# MO-v2-5_MOD-Strips.net
KiCad netlist of a schematic drawn in EAGLE
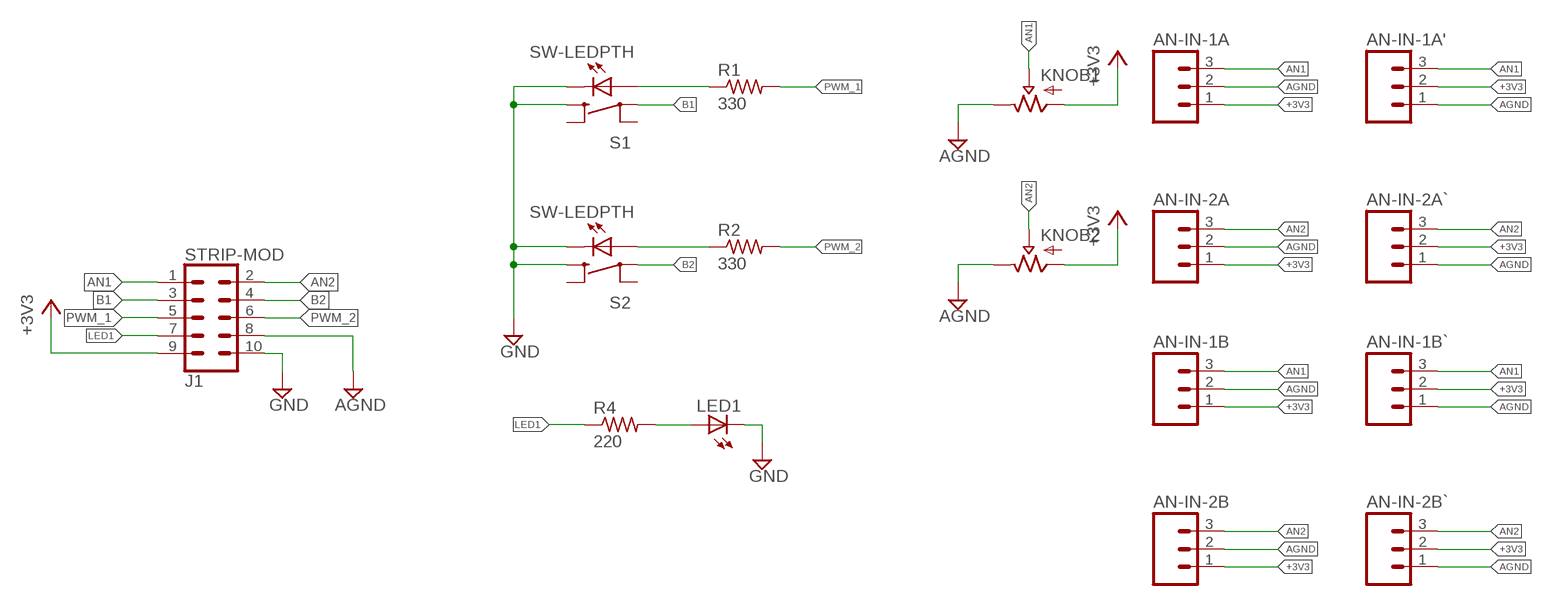
[diagram p0: schematic, sheet 1]

(export (version "E")
  (design (tool "Eeschema 10.0.6"))
  (components
    (comp (ref "AN-IN-1A")
      (value "M031X03_NO_SILK")
      (footprint "eagle-import:1X03_NO_SILK")
      (libsource (lib "eagle-import") (part "M031X03_NO_SILK"))
    )
    (comp (ref "AN-IN-1A'")
      (value "M031X03_NO_SILK")
      (footprint "eagle-import:1X03_NO_SILK")
      (libsource (lib "eagle-import") (part "M031X03_NO_SILK"))
    )
    (comp (ref "AN-IN-1B")
      (value "M031X03_NO_SILK")
      (footprint "eagle-import:1X03_NO_SILK")
      (libsource (lib "eagle-import") (part "M031X03_NO_SILK"))
    )
    (comp (ref "AN-IN-1B`")
      (value "M031X03_NO_SILK")
      (footprint "eagle-import:1X03_NO_SILK")
      (libsource (lib "eagle-import") (part "M031X03_NO_SILK"))
    )
    (comp (ref "AN-IN-2A")
      (value "M031X03_NO_SILK")
      (footprint "eagle-import:1X03_NO_SILK")
      (libsource (lib "eagle-import") (part "M031X03_NO_SILK"))
    )
    (comp (ref "AN-IN-2A`")
      (value "M031X03_NO_SILK")
      (footprint "eagle-import:1X03_NO_SILK")
      (libsource (lib "eagle-import") (part "M031X03_NO_SILK"))
    )
    (comp (ref "AN-IN-2B")
      (value "M031X03_NO_SILK")
      (footprint "eagle-import:1X03_NO_SILK")
      (libsource (lib "eagle-import") (part "M031X03_NO_SILK"))
    )
    (comp (ref "AN-IN-2B`")
      (value "M031X03_NO_SILK")
      (footprint "eagle-import:1X03_NO_SILK")
      (libsource (lib "eagle-import") (part "M031X03_NO_SILK"))
    )
    (comp (ref "KNOB1")
      (value "POTALPHA_RD901")
      (footprint "eagle-import:POT_ALPHA_RD901F-40-(L)R1")
      (libsource (lib "eagle-import") (part "POTALPHA_RD901"))
    )
    (comp (ref "KNOB2")
      (value "POTALPHA_RD901")
      (footprint "eagle-import:POT_ALPHA_RD901F-40-(L)R1")
      (libsource (lib "eagle-import") (part "POTALPHA_RD901"))
    )
    (comp (ref "LED1")
      (value "LED3MM")
      (footprint "eagle-import:LED3MM")
      (libsource (lib "eagle-import") (part "LED3MM"))
    )
    (comp (ref "R1")
      (value "330")
      (footprint "eagle-import:0204_7")
      (libsource (lib "eagle-import") (part "R-US_0204/7"))
    )
    (comp (ref "R2")
      (value "330")
      (footprint "eagle-import:0204_7")
      (libsource (lib "eagle-import") (part "R-US_0204/7"))
    )
    (comp (ref "R4")
      (value "220")
      (footprint "eagle-import:0204_7")
      (libsource (lib "eagle-import") (part "R-US_0204/7"))
    )
    (comp (ref "S1")
      (value "SW-LEDPTH")
      (footprint "eagle-import:SWITCH_TR2-MOMENTARY-LED")
      (libsource (lib "eagle-import") (part "SW-LEDPTH"))
    )
    (comp (ref "S2")
      (value "SW-LEDPTH")
      (footprint "eagle-import:SWITCH_TR2-MOMENTARY-LED")
      (libsource (lib "eagle-import") (part "SW-LEDPTH"))
    )
    (comp (ref "STRIP-MOD")
      (value "J1")
      (footprint "eagle-import:2X5-SHROUDED_LOCK")
      (libsource (lib "eagle-import") (part "CONN_05X2SHD_LOCK"))
    )
  )
  (nets
    (net (code "1") (name "+3V3") (class "Default")
      (node (ref "AN-IN-1A") (pin "1") (pinfunction "1_1") (pintype "passive"))
      (node (ref "AN-IN-1A'") (pin "2") (pinfunction "2_2") (pintype "passive"))
      (node (ref "AN-IN-1B") (pin "1") (pinfunction "1_1") (pintype "passive"))
      (node (ref "AN-IN-1B`") (pin "2") (pinfunction "2_2") (pintype "passive"))
      (node (ref "AN-IN-2A") (pin "1") (pinfunction "1_1") (pintype "passive"))
      (node (ref "AN-IN-2A`") (pin "2") (pinfunction "2_2") (pintype "passive"))
      (node (ref "AN-IN-2B") (pin "1") (pinfunction "1_1") (pintype "passive"))
      (node (ref "AN-IN-2B`") (pin "2") (pinfunction "2_2") (pintype "passive"))
      (node (ref "KNOB1") (pin "1") (pinfunction "IN_1") (pintype "passive"))
      (node (ref "KNOB2") (pin "1") (pinfunction "IN_1") (pintype "passive"))
      (node (ref "STRIP-MOD") (pin "9") (pinfunction "9_9") (pintype "passive"))
    )
    (net (code "2") (name "AGND") (class "Default")
      (node (ref "AN-IN-1A") (pin "2") (pinfunction "2_2") (pintype "passive"))
      (node (ref "AN-IN-1A'") (pin "1") (pinfunction "1_1") (pintype "passive"))
      (node (ref "AN-IN-1B") (pin "2") (pinfunction "2_2") (pintype "passive"))
      (node (ref "AN-IN-1B`") (pin "1") (pinfunction "1_1") (pintype "passive"))
      (node (ref "AN-IN-2A") (pin "2") (pinfunction "2_2") (pintype "passive"))
      (node (ref "AN-IN-2A`") (pin "1") (pinfunction "1_1") (pintype "passive"))
      (node (ref "AN-IN-2B") (pin "2") (pinfunction "2_2") (pintype "passive"))
      (node (ref "AN-IN-2B`") (pin "1") (pinfunction "1_1") (pintype "passive"))
      (node (ref "KNOB1") (pin "3") (pinfunction "OUT_3") (pintype "passive"))
      (node (ref "KNOB2") (pin "3") (pinfunction "OUT_3") (pintype "passive"))
      (node (ref "STRIP-MOD") (pin "8") (pinfunction "8_8") (pintype "passive"))
    )
    (net (code "3") (name "AN1") (class "Default")
      (node (ref "AN-IN-1A") (pin "3") (pinfunction "3_3") (pintype "passive"))
      (node (ref "AN-IN-1A'") (pin "3") (pinfunction "3_3") (pintype "passive"))
      (node (ref "AN-IN-1B") (pin "3") (pinfunction "3_3") (pintype "passive"))
      (node (ref "AN-IN-1B`") (pin "3") (pinfunction "3_3") (pintype "passive"))
      (node (ref "KNOB1") (pin "2") (pinfunction "WIPER_2") (pintype "passive"))
      (node (ref "STRIP-MOD") (pin "1") (pinfunction "1_1") (pintype "passive"))
    )
    (net (code "4") (name "AN2") (class "Default")
      (node (ref "AN-IN-2A") (pin "3") (pinfunction "3_3") (pintype "passive"))
      (node (ref "AN-IN-2A`") (pin "3") (pinfunction "3_3") (pintype "passive"))
      (node (ref "AN-IN-2B") (pin "3") (pinfunction "3_3") (pintype "passive"))
      (node (ref "AN-IN-2B`") (pin "3") (pinfunction "3_3") (pintype "passive"))
      (node (ref "KNOB2") (pin "2") (pinfunction "WIPER_2") (pintype "passive"))
      (node (ref "STRIP-MOD") (pin "2") (pinfunction "2_2") (pintype "passive"))
    )
    (net (code "5") (name "B1") (class "Default")
      (node (ref "S1") (pin "3") (pinfunction "3_3") (pintype "passive"))
      (node (ref "STRIP-MOD") (pin "3") (pinfunction "3_3") (pintype "passive"))
    )
    (net (code "6") (name "B2") (class "Default")
      (node (ref "S2") (pin "3") (pinfunction "3_3") (pintype "passive"))
      (node (ref "STRIP-MOD") (pin "4") (pinfunction "4_4") (pintype "passive"))
    )
    (net (code "7") (name "GND") (class "Default")
      (node (ref "LED1") (pin "K") (pinfunction "C_K") (pintype "passive"))
      (node (ref "S1") (pin "1") (pinfunction "1_1") (pintype "passive"))
      (node (ref "S1") (pin "C") (pinfunction "C_C") (pintype "passive"))
      (node (ref "S2") (pin "1") (pinfunction "1_1") (pintype "passive"))
      (node (ref "S2") (pin "C") (pinfunction "C_C") (pintype "passive"))
      (node (ref "STRIP-MOD") (pin "10") (pinfunction "10_10") (pintype "passive"))
    )
    (net (code "8") (name "LED1") (class "Default")
      (node (ref "R4") (pin "1") (pinfunction "1_1") (pintype "passive"))
      (node (ref "STRIP-MOD") (pin "7") (pinfunction "7_7") (pintype "passive"))
    )
    (net (code "9") (name "Net-(LED1-PadA)") (class "Default")
      (node (ref "LED1") (pin "A") (pinfunction "A_A") (pintype "passive"))
      (node (ref "R4") (pin "2") (pinfunction "2_2") (pintype "passive"))
    )
    (net (code "10") (name "Net-(R1-Pad1)") (class "Default")
      (node (ref "R1") (pin "1") (pinfunction "1_1") (pintype "passive"))
      (node (ref "S1") (pin "A") (pinfunction "A_A") (pintype "passive"))
    )
    (net (code "11") (name "Net-(R2-Pad1)") (class "Default")
      (node (ref "R2") (pin "1") (pinfunction "1_1") (pintype "passive"))
      (node (ref "S2") (pin "A") (pinfunction "A_A") (pintype "passive"))
    )
    (net (code "12") (name "PWM_1") (class "Default")
      (node (ref "R1") (pin "2") (pinfunction "2_2") (pintype "passive"))
      (node (ref "STRIP-MOD") (pin "5") (pinfunction "5_5") (pintype "passive"))
    )
    (net (code "13") (name "PWM_2") (class "Default")
      (node (ref "R2") (pin "2") (pinfunction "2_2") (pintype "passive"))
      (node (ref "STRIP-MOD") (pin "6") (pinfunction "6_6") (pintype "passive"))
    )
    (net (code "14") (name "unconnected-(S1-Pad2)") (class "Default")
      (node (ref "S1") (pin "2") (pinfunction "2_2") (pintype "passive"))
    )
    (net (code "15") (name "unconnected-(S1-Pad4)") (class "Default")
      (node (ref "S1") (pin "4") (pinfunction "4_4") (pintype "passive"))
    )
    (net (code "16") (name "unconnected-(S2-Pad2)") (class "Default")
      (node (ref "S2") (pin "2") (pinfunction "2_2") (pintype "passive"))
    )
    (net (code "17") (name "unconnected-(S2-Pad4)") (class "Default")
      (node (ref "S2") (pin "4") (pinfunction "4_4") (pintype "passive"))
    )
  )
)
